# 06_POWER-INPUT.net
KiCad netlist of a schematic drawn in Altium Designer
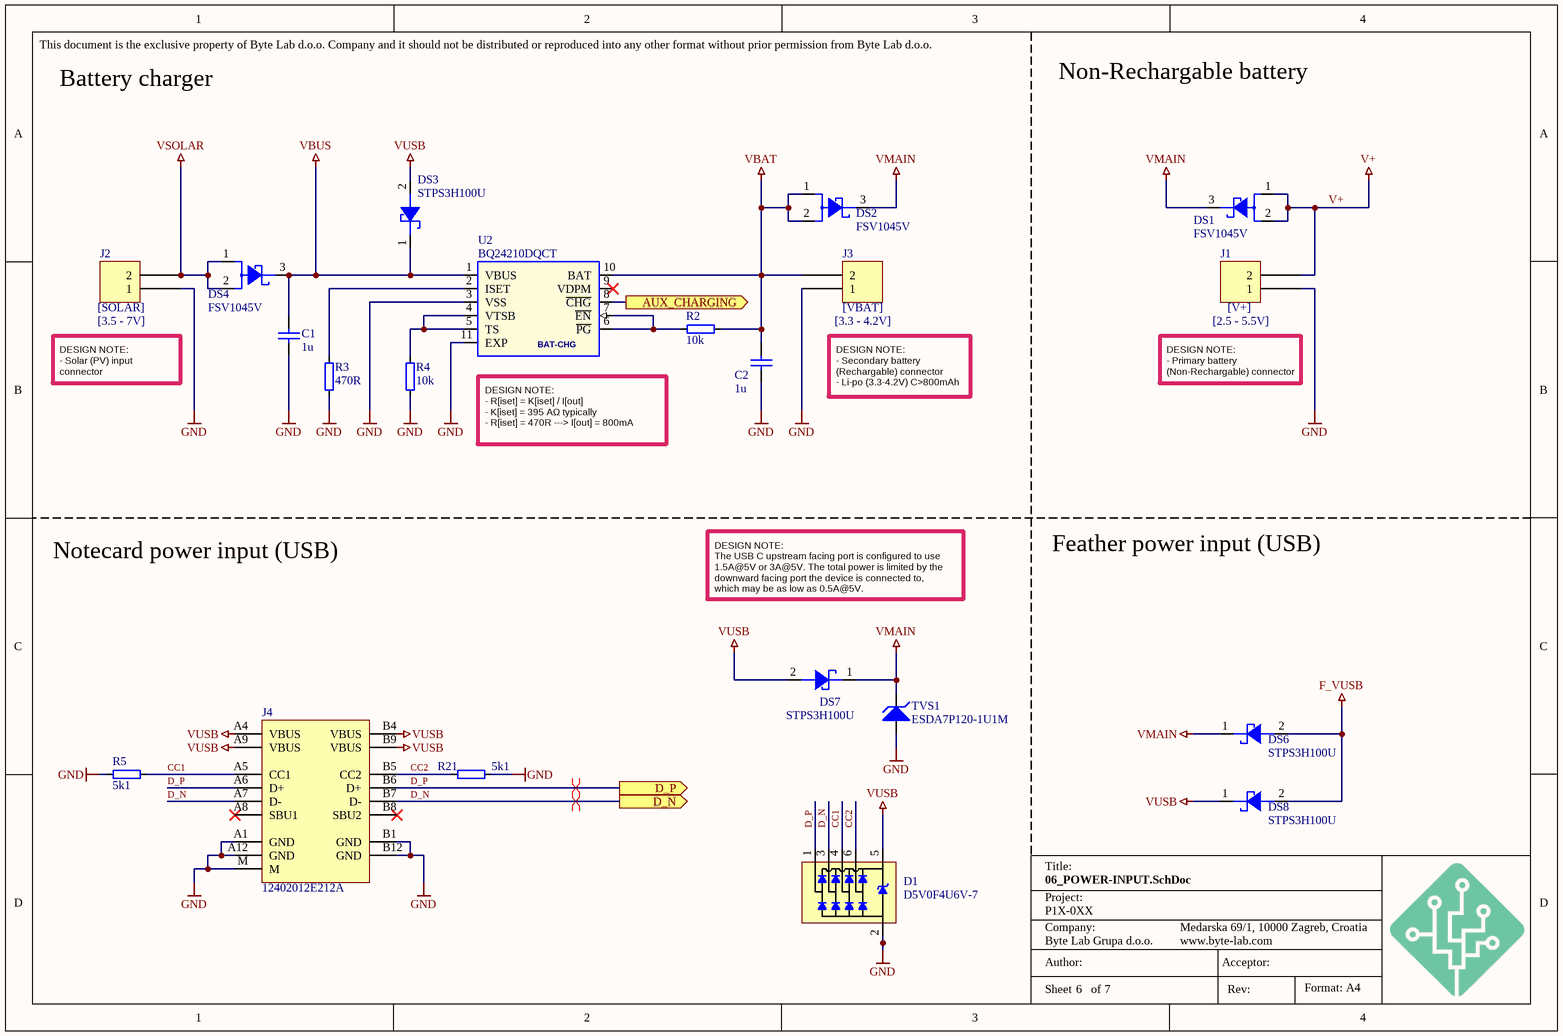
[diagram p0: 06_POWER-INPUT.SchDoc]

(export (version "E")
  (design (tool "Eeschema 10.0.6"))
  (components
    (comp (ref "C1")
      (value "1u")
      (footprint "C-0603")
      (description "Capacitor ceramic 1u ±10% X5R 25V")
      (fields
        (field (name "MANUFACTURER") "Yageo")
        (field (name "BL PART NUMBER") "2006-223")
        (field (name "DRAWN_BY") "Hamin")
        (field (name "CHECKED_BY") "Golubic")
      )
      (libsource (lib "BL_Passive") (part "C0603-1u-25V-X5R"))
    )
    (comp (ref "C2")
      (value "1u")
      (footprint "C-0603")
      (description "Capacitor ceramic 1u ±10% X5R 25V")
      (fields
        (field (name "MANUFACTURER") "Yageo")
        (field (name "BL PART NUMBER") "2006-223")
        (field (name "DRAWN_BY") "Hamin")
        (field (name "CHECKED_BY") "Golubic")
      )
      (libsource (lib "BL_Passive") (part "C0603-1u-25V-X5R"))
    )
    (comp (ref "D1")
      (value "D5V0F4U6V-7")
      (footprint "SOT-563")
      (description "TVS DIODE 5.5VWM 12VC SOT563")
      (fields
        (field (name "BL PART NUMBER") "2010-391")
        (field (name "MANUFACTURER") "Diodes Incorporated")
        (field (name "DRAWN_BY") "Duracic")
        (field (name "CHECKED_BY") "Hrastic")
      )
      (libsource (lib "BL_Active") (part "D5V0F4U6V-7"))
    )
    (comp (ref "DS1")
      (value "FSV1045V")
      (footprint "TO277-3")
      (description "DIODO SCHOTTKY 10A 45V FSV1045V TO277-3 SMT")
      (fields
        (field (name "BL PART NUMBER") "2007-712")
        (field (name "MANUFACTURER") "onsemi")
        (field (name "DRAWN_BY") "Blues Wireless")
      )
      (libsource (lib "n21-p2") (part "SCHOTTKY - FSV1045V - 10A/45V"))
    )
    (comp (ref "DS2")
      (value "FSV1045V")
      (footprint "TO277-3")
      (description "DIODO SCHOTTKY 10A 45V FSV1045V TO277-3 SMT")
      (fields
        (field (name "BL PART NUMBER") "2007-712")
        (field (name "MANUFACTURER") "onsemi")
        (field (name "DRAWN_BY") "Blues Wireless")
      )
      (libsource (lib "n21-p2") (part "SCHOTTKY - FSV1045V - 10A/45V"))
    )
    (comp (ref "DS3")
      (value "STPS3H100U")
      (footprint "SMB")
      (description "DIODO SCHOTTKY 3A 100V STPS3H100U SMB SMT")
      (fields
        (field (name "MANUFACTURER") "STMicroelectronics")
        (field (name "BL PART NUMBER") "2007-711")
        (field (name "DRAWN_BY") "Blues Wireless")
      )
      (libsource (lib "n21-p2") (part "SCHOTTKY-STPS3H100U - 3A/100V"))
    )
    (comp (ref "DS4")
      (value "FSV1045V")
      (footprint "TO277-3")
      (description "DIODO SCHOTTKY 10A 45V FSV1045V TO277-3 SMT")
      (fields
        (field (name "BL PART NUMBER") "2007-712")
        (field (name "MANUFACTURER") "onsemi")
        (field (name "DRAWN_BY") "Blues Wireless")
      )
      (libsource (lib "n21-p2") (part "SCHOTTKY - FSV1045V - 10A/45V"))
    )
    (comp (ref "DS6")
      (value "STPS3H100U")
      (footprint "SMB")
      (description "DIODO SCHOTTKY 3A 100V STPS3H100U SMB SMT")
      (fields
        (field (name "MANUFACTURER") "STMicroelectronics")
        (field (name "BL PART NUMBER") "2007-711")
        (field (name "DRAWN_BY") "Blues Wireless")
      )
      (libsource (lib "n21-p2") (part "SCHOTTKY-STPS3H100U - 3A/100V"))
    )
    (comp (ref "DS7")
      (value "STPS3H100U")
      (footprint "SMB")
      (description "DIODO SCHOTTKY 3A 100V STPS3H100U SMB SMT")
      (fields
        (field (name "MANUFACTURER") "STMicroelectronics")
        (field (name "BL PART NUMBER") "2007-711")
        (field (name "DRAWN_BY") "Blues Wireless")
      )
      (libsource (lib "n21-p2") (part "SCHOTTKY-STPS3H100U - 3A/100V"))
    )
    (comp (ref "DS8")
      (value "STPS3H100U")
      (footprint "SMB")
      (description "DIODO SCHOTTKY 3A 100V STPS3H100U SMB SMT")
      (fields
        (field (name "MANUFACTURER") "STMicroelectronics")
        (field (name "BL PART NUMBER") "2007-711")
        (field (name "DRAWN_BY") "Blues Wireless")
      )
      (libsource (lib "n21-p2") (part "SCHOTTKY-STPS3H100U - 3A/100V"))
    )
    (comp (ref "J1")
      (value "S2BPHSM4TBLFSN")
      (footprint "JST S2B-PH-SM4-TB")
      (description "PH SMT SIDE ENTRY HDR 2W")
      (fields
        (field (name "MANUFACTURER") "JST")
        (field (name "MANUFACTURER PART NUMBER") "S2B-PH-SM4-K-TB (LF)(SN)")
        (field (name "DRAWN_BY") "Blues Wireless")
      )
      (libsource (lib "n21-p2") (part "S2BPHSM4TBLFSN"))
    )
    (comp (ref "J2")
      (value "S2BPHSM4TBLFSN")
      (footprint "JST S2B-PH-SM4-TB")
      (description "PH SMT SIDE ENTRY HDR 2W")
      (fields
        (field (name "MANUFACTURER") "JST")
        (field (name "MANUFACTURER PART NUMBER") "S2B-PH-SM4-K-TB (LF)(SN)")
        (field (name "DRAWN_BY") "Blues Wireless")
      )
      (libsource (lib "n21-p2") (part "S2BPHSM4TBLFSN"))
    )
    (comp (ref "J3")
      (value "S2BPHSM4TBLFSN")
      (footprint "JST S2B-PH-SM4-TB")
      (description "PH SMT SIDE ENTRY HDR 2W")
      (fields
        (field (name "MANUFACTURER") "JST")
        (field (name "MANUFACTURER PART NUMBER") "S2B-PH-SM4-K-TB (LF)(SN)")
        (field (name "DRAWN_BY") "Blues Wireless")
      )
      (libsource (lib "") (part "S2BPHSM4TBLFSN_1"))
    )
    (comp (ref "J4")
      (value "12402012E212A")
      (footprint "CONN_12402012E212A")
      (description "CONN RCP USB2.0 TYP C 24P SMD RA")
      (fields
        (field (name "BL PART NUMBER") "2008-437")
        (field (name "MANUFACTURER") "Amphenol")
        (field (name "DRAWN_BY") "Anic-Ivicic")
        (field (name "CHECKED_BY") "Hlupic")
      )
      (libsource (lib "BL_Mechanical") (part "Conn USB C 12402012E212A"))
    )
    (comp (ref "R2")
      (value "10k")
      (footprint "R-0402")
      (description "Resistor 10k ±1% 0402")
      (fields
        (field (name "BL PART NUMBER") "2000-729")
        (field (name "CHECKED_BY") "Dodig")
        (field (name "DRAWN_BY") "Puskar")
      )
      (libsource (lib "BL_Passive") (part "R0402-10k-1"))
    )
    (comp (ref "R3")
      (value "470R")
      (footprint "R-0402")
      (description "Resistor 470R ±1% 0402")
      (fields
        (field (name "BL PART NUMBER") "2001-420")
        (field (name "CHECKED_BY") "Marsic")
        (field (name "DRAWN_BY") "Hamin")
      )
      (libsource (lib "BL_Passive") (part "R0402-470R-1"))
    )
    (comp (ref "R4")
      (value "10k")
      (footprint "R-0402")
      (description "Resistor 10k ±1% 0402")
      (fields
        (field (name "BL PART NUMBER") "2000-729")
        (field (name "CHECKED_BY") "Dodig")
        (field (name "DRAWN_BY") "Puskar")
      )
      (libsource (lib "BL_Passive") (part "R0402-10k-1"))
    )
    (comp (ref "R5")
      (value "5k1")
      (footprint "BL_Passive:R-0402")
      (description "Resistor 5k1 ±1% 0402")
      (fields
        (field (name "BL PART NUMBER") "2004-098")
        (field (name "CHECKED_BY") "Hamin")
        (field (name "DRAWN_BY") "PuskarJ")
      )
      (libsource (lib "BL_Passive") (part "R0402-5k1-1"))
    )
    (comp (ref "R21")
      (value "5k1")
      (footprint "BL_Passive:R-0402")
      (description "Resistor 5k1 ±1% 0402")
      (fields
        (field (name "BL PART NUMBER") "2004-098")
        (field (name "CHECKED_BY") "Hamin")
        (field (name "DRAWN_BY") "PuskarJ")
      )
      (libsource (lib "BL_Passive") (part "R0402-5k1-1"))
    )
    (comp (ref "TVS1")
      (value "ESDA7P120-1U1M")
      (footprint "DIOC_160X100X60")
      (description "TVS DIODE 5.5VWM 11.5VC 1610")
      (fields
        (field (name "MANUFACTURER") "STMicroelectronics")
        (field (name "BL PART NUMBER") "2007-378")
        (field (name "CHECKED_BY") "Kvesic")
        (field (name "DRAWN_BY") "Duracic")
      )
      (libsource (lib "BL_Active") (part "ESDA7P120-1U1M"))
    )
    (comp (ref "U2")
      (value "BQ24210DQCT")
      (footprint "WSON10-EXP")
      (description "INTEGRATO BQ24210DQCT WSON10 TEXAS SMT")
      (fields
        (field (name "BL PART NUMBER") "2005-527")
        (field (name "MANUFACTURER") "Texas Instruments")
        (field (name "DRAWN_BY") "Blues Wireless")
      )
      (libsource (lib "n21-p2") (part "BAT-CHARGE - BQ24210DQCT"))
    )
  )
  (nets
    (net (code "1") (name "/AUX_CHARGING") (class "Default")
      (node (ref "U2") (pin "8") (pinfunction "~{CHG}_8") (pintype "open_collector"))
    )
    (net (code "2") (name "/CC1") (class "Default")
      (node (ref "D1") (pin "4") (pinfunction "CH3_4") (pintype "passive"))
      (node (ref "J4") (pin "A5") (pinfunction "CC1_A5") (pintype "passive"))
      (node (ref "R5") (pin "2") (pintype "passive"))
    )
    (net (code "3") (name "/CC2") (class "Default")
      (node (ref "D1") (pin "6") (pinfunction "CH4_6") (pintype "passive"))
      (node (ref "J4") (pin "B5") (pinfunction "CC2_B5") (pintype "passive"))
      (node (ref "R21") (pin "1") (pintype "passive"))
    )
    (net (code "4") (name "/D_N") (class "Default")
      (node (ref "D1") (pin "3") (pinfunction "CH2_3") (pintype "passive"))
      (node (ref "J4") (pin "A7") (pinfunction "D-_A7") (pintype "passive"))
      (node (ref "J4") (pin "B7") (pinfunction "D-_B7") (pintype "passive"))
    )
    (net (code "5") (name "/D_P") (class "Default")
      (node (ref "D1") (pin "1") (pinfunction "CH1_1") (pintype "passive"))
      (node (ref "J4") (pin "A6") (pinfunction "D+_A6") (pintype "passive"))
      (node (ref "J4") (pin "B6") (pinfunction "D+_B6") (pintype "passive"))
    )
    (net (code "6") (name "F_VUSB") (class "Default")
      (node (ref "DS6") (pin "2") (pinfunction "A_2") (pintype "passive"))
      (node (ref "DS8") (pin "2") (pinfunction "A_2") (pintype "passive"))
    )
    (net (code "7") (name "GND") (class "Default")
      (node (ref "C1") (pin "1") (pinfunction "1_1") (pintype "passive"))
      (node (ref "C2") (pin "1") (pinfunction "1_1") (pintype "passive"))
      (node (ref "D1") (pin "2") (pinfunction "GND_2") (pintype "power_in"))
      (node (ref "J1") (pin "1") (pinfunction "1_1") (pintype "passive"))
      (node (ref "J2") (pin "1") (pinfunction "1_1") (pintype "passive"))
      (node (ref "J3") (pin "1") (pinfunction "1_1") (pintype "passive"))
      (node (ref "J4") (pin "A1") (pinfunction "GND_A1") (pintype "power_in"))
      (node (ref "J4") (pin "A12") (pinfunction "GND_A12") (pintype "power_in"))
      (node (ref "J4") (pin "B1") (pinfunction "GND_B1") (pintype "power_in"))
      (node (ref "J4") (pin "B12") (pinfunction "GND_B12") (pintype "power_in"))
      (node (ref "J4") (pin "M") (pinfunction "M_M") (pintype "power_in"))
      (node (ref "R21") (pin "2") (pintype "passive"))
      (node (ref "R3") (pin "1") (pintype "passive"))
      (node (ref "R4") (pin "1") (pintype "passive"))
      (node (ref "R5") (pin "1") (pintype "passive"))
      (node (ref "TVS1") (pin "1") (pinfunction "A_1") (pintype "passive"))
      (node (ref "U2") (pin "11") (pinfunction "EXP_11") (pintype "passive"))
      (node (ref "U2") (pin "3") (pinfunction "VSS_3") (pintype "power_in"))
    )
    (net (code "8") (name "Net-(U2-ISET)") (class "Default")
      (node (ref "R3") (pin "2") (pintype "passive"))
      (node (ref "U2") (pin "2") (pinfunction "ISET_2") (pintype "passive"))
    )
    (net (code "9") (name "Net-(U2-TS)") (class "Default")
      (node (ref "R4") (pin "2") (pintype "passive"))
      (node (ref "U2") (pin "4") (pinfunction "VTSB_4") (pintype "passive"))
      (node (ref "U2") (pin "5") (pinfunction "TS_5") (pintype "passive"))
    )
    (net (code "10") (name "Net-(U2-~{EN})") (class "Default")
      (node (ref "R2") (pin "1") (pintype "passive"))
      (node (ref "U2") (pin "6") (pinfunction "~{PG}_6") (pintype "open_collector"))
      (node (ref "U2") (pin "7") (pinfunction "~{EN}_7") (pintype "input"))
    )
    (net (code "11") (name "V+") (class "Default")
      (node (ref "DS1") (pin "1") (pinfunction "A1_1") (pintype "passive"))
      (node (ref "DS1") (pin "2") (pinfunction "A2_2") (pintype "passive"))
      (node (ref "J1") (pin "2") (pinfunction "2_2") (pintype "passive"))
    )
    (net (code "12") (name "VBAT") (class "Default")
      (node (ref "C2") (pin "2") (pinfunction "2_2") (pintype "passive"))
      (node (ref "DS2") (pin "1") (pinfunction "A1_1") (pintype "passive"))
      (node (ref "DS2") (pin "2") (pinfunction "A2_2") (pintype "passive"))
      (node (ref "J3") (pin "2") (pinfunction "2_2") (pintype "passive"))
      (node (ref "R2") (pin "2") (pintype "passive"))
      (node (ref "U2") (pin "10") (pinfunction "BAT_10") (pintype "power_in"))
    )
    (net (code "13") (name "VBUS") (class "Default")
      (node (ref "C1") (pin "2") (pinfunction "2_2") (pintype "passive"))
      (node (ref "DS3") (pin "1") (pinfunction "C_1") (pintype "passive"))
      (node (ref "DS4") (pin "3") (pinfunction "C_3") (pintype "passive"))
      (node (ref "U2") (pin "1") (pinfunction "VBUS_1") (pintype "power_in"))
    )
    (net (code "14") (name "VMAIN") (class "Default")
      (node (ref "DS1") (pin "3") (pinfunction "C_3") (pintype "passive"))
      (node (ref "DS2") (pin "3") (pinfunction "C_3") (pintype "passive"))
      (node (ref "DS6") (pin "1") (pinfunction "C_1") (pintype "passive"))
      (node (ref "DS7") (pin "1") (pinfunction "C_1") (pintype "passive"))
      (node (ref "TVS1") (pin "2") (pinfunction "K_2") (pintype "passive"))
    )
    (net (code "15") (name "VSOLAR") (class "Default")
      (node (ref "DS4") (pin "1") (pinfunction "A1_1") (pintype "passive"))
      (node (ref "DS4") (pin "2") (pinfunction "A2_2") (pintype "passive"))
      (node (ref "J2") (pin "2") (pinfunction "2_2") (pintype "passive"))
    )
    (net (code "16") (name "VUSB") (class "Default")
      (node (ref "D1") (pin "5") (pinfunction "VDD_5") (pintype "power_in"))
      (node (ref "DS3") (pin "2") (pinfunction "A_2") (pintype "passive"))
      (node (ref "DS7") (pin "2") (pinfunction "A_2") (pintype "passive"))
      (node (ref "DS8") (pin "1") (pinfunction "C_1") (pintype "passive"))
      (node (ref "J4") (pin "A4") (pinfunction "VBUS_A4") (pintype "power_in"))
      (node (ref "J4") (pin "A9") (pinfunction "VBUS_A9") (pintype "power_in"))
      (node (ref "J4") (pin "B4") (pinfunction "VBUS_B4") (pintype "power_in"))
      (node (ref "J4") (pin "B9") (pinfunction "VBUS_B9") (pintype "power_in"))
    )
    (net (code "17") (name "unconnected-(J4-SBU1-PadA8)") (class "Default")
      (node (ref "J4") (pin "A8") (pinfunction "SBU1_A8") (pintype "passive+no_connect"))
    )
    (net (code "18") (name "unconnected-(J4-SBU2-PadB8)") (class "Default")
      (node (ref "J4") (pin "B8") (pinfunction "SBU2_B8") (pintype "passive+no_connect"))
    )
    (net (code "19") (name "unconnected-(U2-VDPM-Pad9)") (class "Default")
      (node (ref "U2") (pin "9") (pinfunction "VDPM_9") (pintype "passive+no_connect"))
    )
  )
)
